# hs-64-spi.net
KiCad netlist of a schematic drawn in EAGLE
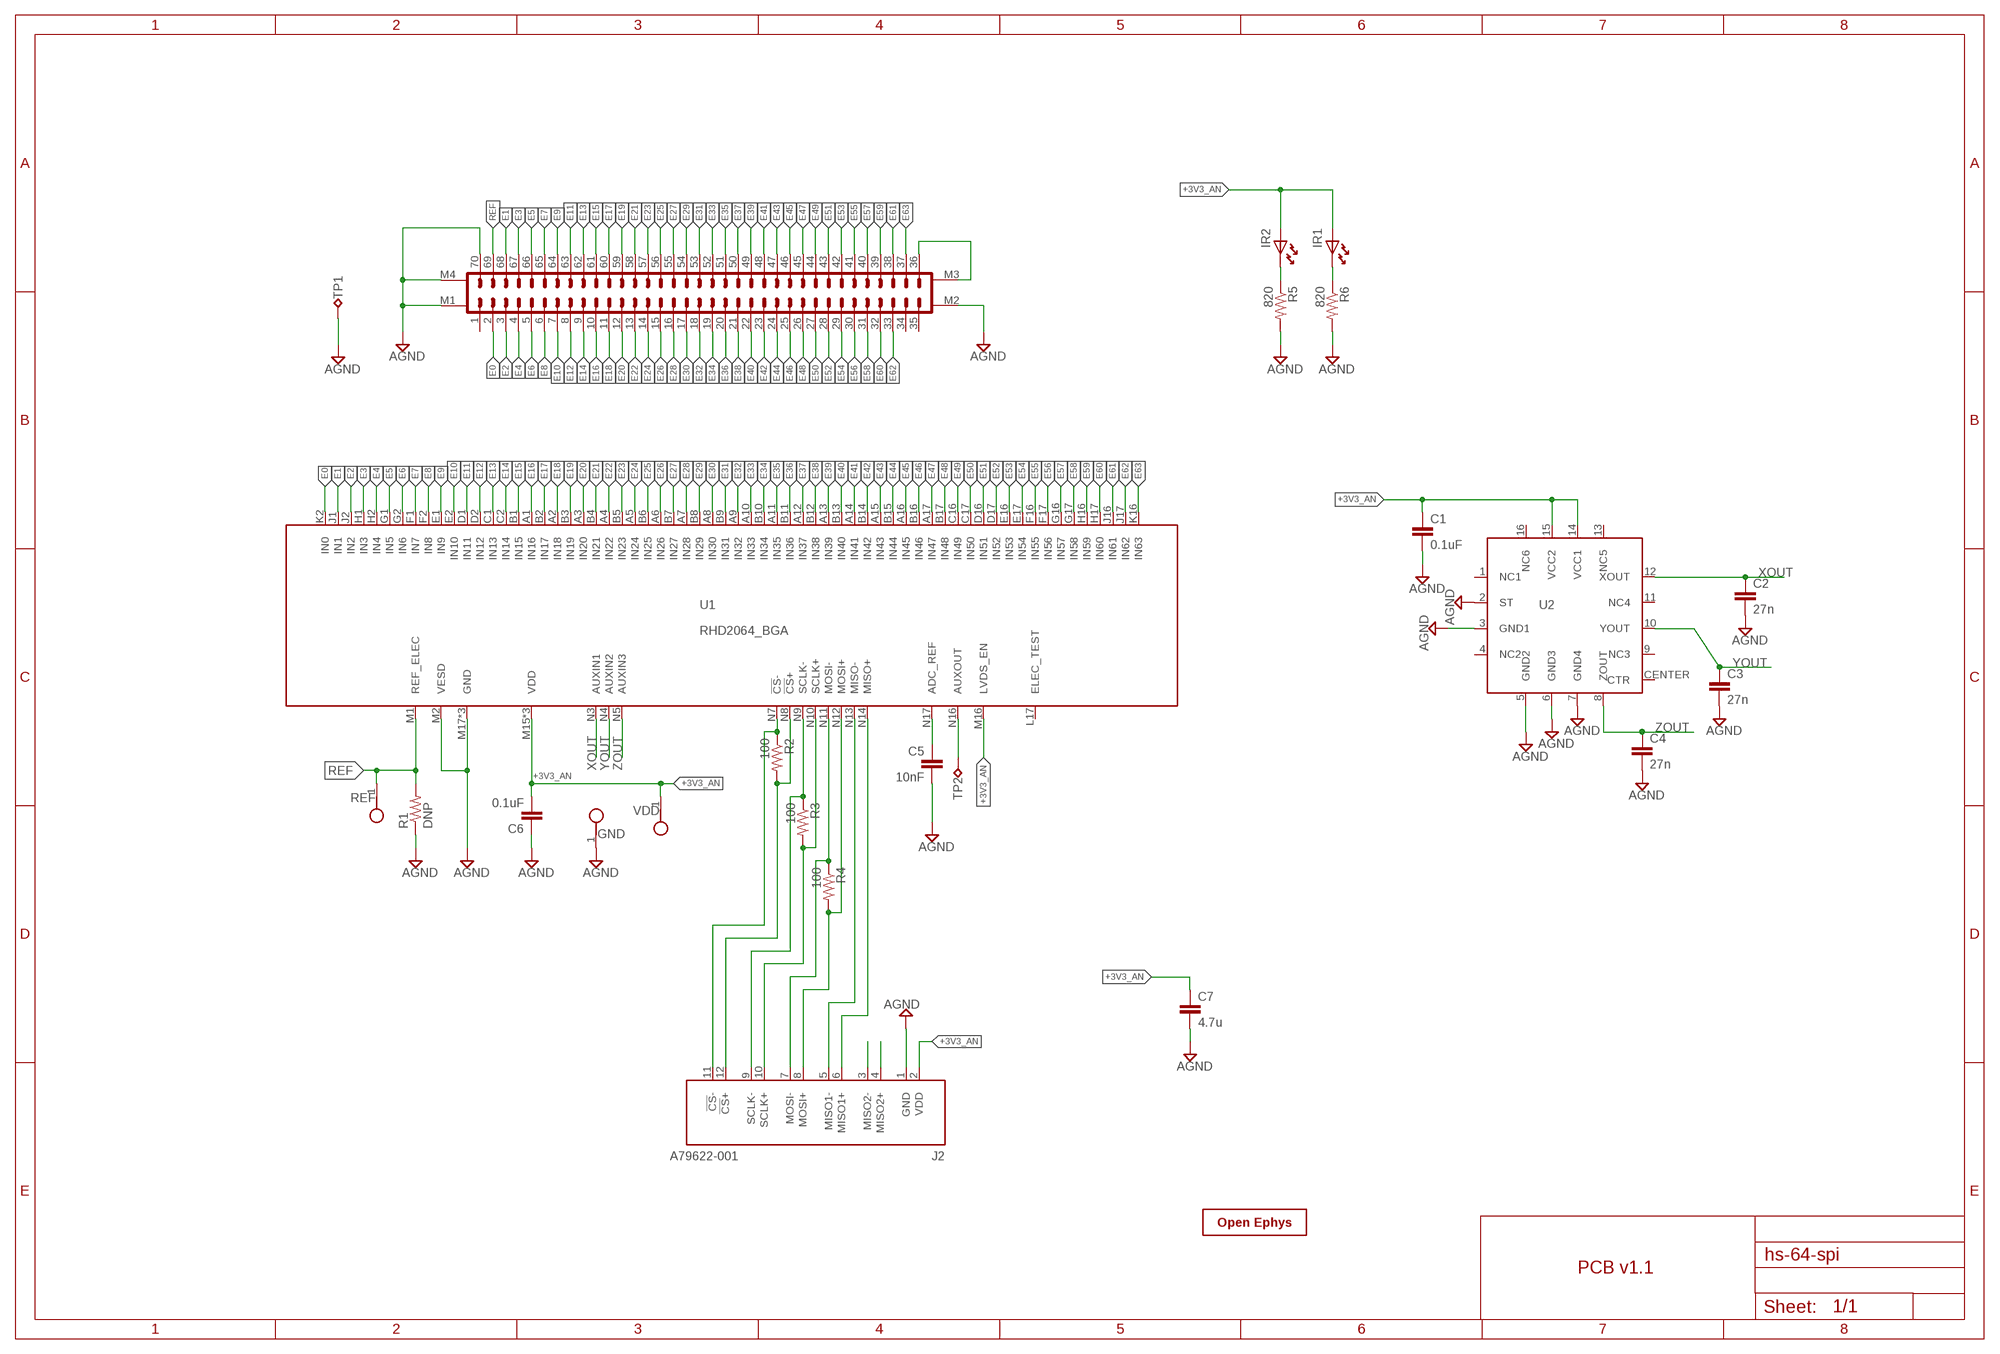
[diagram p0: schematic, sheet 1]

(export (version "E")
  (design (tool "Eeschema 10.0.6"))
  (components
    (comp (ref "C1")
      (value "0.1uF")
      (footprint "eagle-import:0402")
      (libsource (lib "eagle-import") (part "C_0402"))
    )
    (comp (ref "C2")
      (value "27n")
      (footprint "eagle-import:0402")
      (libsource (lib "eagle-import") (part "C_0402"))
    )
    (comp (ref "C3")
      (value "27n")
      (footprint "eagle-import:0402")
      (libsource (lib "eagle-import") (part "C_0402"))
    )
    (comp (ref "C4")
      (value "27n")
      (footprint "eagle-import:0402")
      (libsource (lib "eagle-import") (part "C_0402"))
    )
    (comp (ref "C5")
      (value "10nF")
      (footprint "eagle-import:0402T")
      (fields (field (name "PARTNO") "GRM033R71E103KE14D"))
      (libsource (lib "eagle-import") (part "C_0402T"))
    )
    (comp (ref "C6")
      (value "0.1uF")
      (footprint "eagle-import:0402T")
      (libsource (lib "eagle-import") (part "C_0402T"))
    )
    (comp (ref "C7")
      (value "4.7u")
      (footprint "eagle-import:0402")
      (libsource (lib "eagle-import") (part "C_0402"))
    )
    (comp (ref "GND")
      (value "TESTPOINT_SMALL")
      (footprint "eagle-import:TESTPOINT_SMALL")
      (libsource (lib "eagle-import") (part "TESTPOINT_SMALL"))
    )
    (comp (ref "IR1")
      (value "LEDHAND")
      (footprint "eagle-import:LED_HAND")
      (libsource (lib "eagle-import") (part "LEDHAND"))
    )
    (comp (ref "IR2")
      (value "LEDHAND")
      (footprint "eagle-import:LED_HAND")
      (libsource (lib "eagle-import") (part "LEDHAND"))
    )
    (comp (ref "J1")
      (value "DF40C-70DP-0.4V(51)")
      (footprint "eagle-import:DF40-70HEAD-LESS-SILK")
      (libsource (lib "eagle-import") (part "PINHD-2X35+4DF40-70HEAD-LESS-SILK"))
    )
    (comp (ref "J2")
      (value "A79622-001")
      (footprint "eagle-import:A79622-001")
      (libsource (lib "eagle-import") (part "A79622-001"))
    )
    (comp (ref "R1")
      (value "DNP")
      (footprint "eagle-import:0603")
      (fields (field (name "MPN") "ERJ-3EKFxxxxV"))
      (libsource (lib "eagle-import") (part "R_0603"))
    )
    (comp (ref "R2")
      (value "100")
      (footprint "eagle-import:0402")
      (libsource (lib "eagle-import") (part "R_0402"))
    )
    (comp (ref "R3")
      (value "100")
      (footprint "eagle-import:0402")
      (libsource (lib "eagle-import") (part "R_0402"))
    )
    (comp (ref "R4")
      (value "100")
      (footprint "eagle-import:0402")
      (libsource (lib "eagle-import") (part "R_0402"))
    )
    (comp (ref "R5")
      (value "820")
      (footprint "eagle-import:0402")
      (libsource (lib "eagle-import") (part "R_0402"))
    )
    (comp (ref "R6")
      (value "820")
      (footprint "eagle-import:0402")
      (libsource (lib "eagle-import") (part "R_0402"))
    )
    (comp (ref "REF")
      (value "TESTPOINT_SMALL")
      (footprint "eagle-import:TESTPOINT_SMALL")
      (libsource (lib "eagle-import") (part "TESTPOINT_SMALL"))
    )
    (comp (ref "TP1")
      (value "VCC")
      (footprint "eagle-import:TP07R")
      (libsource (lib "eagle-import") (part "TPTP07R"))
    )
    (comp (ref "TP2")
      (value "VCC")
      (footprint "eagle-import:TP07R")
      (libsource (lib "eagle-import") (part "TPTP07R"))
    )
    (comp (ref "U1")
      (value "RHD2064_BGA")
      (footprint "eagle-import:BGA104_0.5MM")
      (libsource (lib "eagle-import") (part "RHD2164_BGA_BGA"))
    )
    (comp (ref "U2")
      (value "ADXL335_IDAX")
      (footprint "eagle-import:ADXL335_IDAX")
      (libsource (lib "eagle-import") (part "ADXL335_IDAX"))
    )
    (comp (ref "VDD")
      (value "TESTPOINT_SMALL")
      (footprint "eagle-import:TESTPOINT_SMALL")
      (libsource (lib "eagle-import") (part "TESTPOINT_SMALL"))
    )
    (comp (ref "X")
      (value "OE-LOGO_3.5X2.5")
      (footprint "eagle-import:OE-LOGO-3.5X2.5")
      (libsource (lib "eagle-import") (part "OE-LOGO_3.5X2.5"))
    )
  )
  (nets
    (net (code "1") (name "+3V3_AN") (class "Default")
      (node (ref "C1") (pin "1") (pinfunction "1_1") (pintype "passive"))
      (node (ref "C6") (pin "2") (pinfunction "2_2") (pintype "passive"))
      (node (ref "C7") (pin "1") (pinfunction "1_1") (pintype "passive"))
      (node (ref "IR1") (pin "A") (pinfunction "A_A") (pintype "bidirectional"))
      (node (ref "IR2") (pin "A") (pinfunction "A_A") (pintype "bidirectional"))
      (node (ref "J2") (pin "2") (pinfunction "VDD_2") (pintype "bidirectional"))
      (node (ref "U1") (pin "M15") (pinfunction "VDD_M15") (pintype "power_in"))
      (node (ref "U1") (pin "M16") (pinfunction "LVDS_EN_M16") (pintype "input"))
      (node (ref "U1") (pin "N15") (pinfunction "VDD_N15") (pintype "power_in"))
      (node (ref "U1") (pin "N2") (pinfunction "VDD_N2") (pintype "power_in"))
      (node (ref "U2") (pin "14") (pinfunction "VCC1_14") (pintype "power_in"))
      (node (ref "U2") (pin "15") (pinfunction "VCC2_15") (pintype "power_in"))
      (node (ref "VDD") (pin "1") (pinfunction "1_1") (pintype "passive"))
    )
    (net (code "2") (name "/XOUT") (class "Default")
      (node (ref "C2") (pin "1") (pinfunction "1_1") (pintype "passive"))
      (node (ref "U1") (pin "N3") (pinfunction "AUXIN1_N3") (pintype "input"))
      (node (ref "U2") (pin "12") (pinfunction "XOUT_12") (pintype "output"))
    )
    (net (code "3") (name "/YOUT") (class "Default")
      (node (ref "C3") (pin "1") (pinfunction "1_1") (pintype "passive"))
      (node (ref "U1") (pin "N4") (pinfunction "AUXIN2_N4") (pintype "input"))
      (node (ref "U2") (pin "10") (pinfunction "YOUT_10") (pintype "output"))
    )
    (net (code "4") (name "/ZOUT") (class "Default")
      (node (ref "C4") (pin "1") (pinfunction "1_1") (pintype "passive"))
      (node (ref "U1") (pin "N5") (pinfunction "AUXIN3_N5") (pintype "input"))
      (node (ref "U2") (pin "8") (pinfunction "ZOUT_8") (pintype "output"))
    )
    (net (code "5") (name "AGND") (class "Default")
      (node (ref "C1") (pin "2") (pinfunction "2_2") (pintype "passive"))
      (node (ref "C2") (pin "2") (pinfunction "2_2") (pintype "passive"))
      (node (ref "C3") (pin "2") (pinfunction "2_2") (pintype "passive"))
      (node (ref "C4") (pin "2") (pinfunction "2_2") (pintype "passive"))
      (node (ref "C5") (pin "2") (pinfunction "2_2") (pintype "passive"))
      (node (ref "C6") (pin "1") (pinfunction "1_1") (pintype "passive"))
      (node (ref "C7") (pin "2") (pinfunction "2_2") (pintype "passive"))
      (node (ref "GND") (pin "1") (pinfunction "1_1") (pintype "passive"))
      (node (ref "J1") (pin "70") (pinfunction "70_70") (pintype "bidirectional"))
      (node (ref "J1") (pin "M1") (pinfunction "M1_M1") (pintype "bidirectional"))
      (node (ref "J1") (pin "M2") (pinfunction "M2_M2") (pintype "bidirectional"))
      (node (ref "J1") (pin "M4") (pinfunction "M4_M4") (pintype "bidirectional"))
      (node (ref "J2") (pin "1") (pinfunction "GND_1") (pintype "power_in"))
      (node (ref "R1") (pin "1") (pinfunction "1_1") (pintype "passive"))
      (node (ref "R5") (pin "2") (pinfunction "2_2") (pintype "passive"))
      (node (ref "R6") (pin "2") (pinfunction "2_2") (pintype "passive"))
      (node (ref "TP1") (pin "TP") (pinfunction "TP_TP") (pintype "bidirectional"))
      (node (ref "U1") (pin "M17") (pinfunction "GND_M17") (pintype "power_in"))
      (node (ref "U1") (pin "M2") (pinfunction "VESD_M2") (pintype "power_in"))
      (node (ref "U1") (pin "N1") (pinfunction "GND_N1") (pintype "power_in"))
      (node (ref "U1") (pin "N6") (pinfunction "GND_N6") (pintype "power_in"))
      (node (ref "U2") (pin "2") (pinfunction "ST_2") (pintype "input"))
      (node (ref "U2") (pin "3") (pinfunction "GND1_3") (pintype "power_in"))
      (node (ref "U2") (pin "5") (pinfunction "GND2_5") (pintype "power_in"))
      (node (ref "U2") (pin "6") (pinfunction "GND3_6") (pintype "power_in"))
      (node (ref "U2") (pin "7") (pinfunction "GND4_7") (pintype "power_in"))
    )
    (net (code "6") (name "E0") (class "Default")
      (node (ref "J1") (pin "2") (pinfunction "2_2") (pintype "bidirectional"))
      (node (ref "U1") (pin "K2") (pinfunction "IN0_K2") (pintype "input"))
    )
    (net (code "7") (name "E1") (class "Default")
      (node (ref "J1") (pin "68") (pinfunction "68_68") (pintype "bidirectional"))
      (node (ref "U1") (pin "J1") (pinfunction "IN1_J1") (pintype "input"))
    )
    (net (code "8") (name "E2") (class "Default")
      (node (ref "J1") (pin "3") (pinfunction "3_3") (pintype "bidirectional"))
      (node (ref "U1") (pin "J2") (pinfunction "IN2_J2") (pintype "input"))
    )
    (net (code "9") (name "E3") (class "Default")
      (node (ref "J1") (pin "67") (pinfunction "67_67") (pintype "bidirectional"))
      (node (ref "U1") (pin "H1") (pinfunction "IN3_H1") (pintype "input"))
    )
    (net (code "10") (name "E4") (class "Default")
      (node (ref "J1") (pin "4") (pinfunction "4_4") (pintype "bidirectional"))
      (node (ref "U1") (pin "H2") (pinfunction "IN4_H2") (pintype "input"))
    )
    (net (code "11") (name "E5") (class "Default")
      (node (ref "J1") (pin "66") (pinfunction "66_66") (pintype "bidirectional"))
      (node (ref "U1") (pin "G1") (pinfunction "IN5_G1") (pintype "input"))
    )
    (net (code "12") (name "E6") (class "Default")
      (node (ref "J1") (pin "5") (pinfunction "5_5") (pintype "bidirectional"))
      (node (ref "U1") (pin "G2") (pinfunction "IN6_G2") (pintype "input"))
    )
    (net (code "13") (name "E7") (class "Default")
      (node (ref "J1") (pin "65") (pinfunction "65_65") (pintype "bidirectional"))
      (node (ref "U1") (pin "F1") (pinfunction "IN7_F1") (pintype "input"))
    )
    (net (code "14") (name "E8") (class "Default")
      (node (ref "J1") (pin "6") (pinfunction "6_6") (pintype "bidirectional"))
      (node (ref "U1") (pin "F2") (pinfunction "IN8_F2") (pintype "input"))
    )
    (net (code "15") (name "E9") (class "Default")
      (node (ref "J1") (pin "64") (pinfunction "64_64") (pintype "bidirectional"))
      (node (ref "U1") (pin "E1") (pinfunction "IN9_E1") (pintype "input"))
    )
    (net (code "16") (name "E10") (class "Default")
      (node (ref "J1") (pin "7") (pinfunction "7_7") (pintype "bidirectional"))
      (node (ref "U1") (pin "E2") (pinfunction "IN10_E2") (pintype "input"))
    )
    (net (code "17") (name "E11") (class "Default")
      (node (ref "J1") (pin "63") (pinfunction "63_63") (pintype "bidirectional"))
      (node (ref "U1") (pin "D1") (pinfunction "IN11_D1") (pintype "input"))
    )
    (net (code "18") (name "E12") (class "Default")
      (node (ref "J1") (pin "8") (pinfunction "8_8") (pintype "bidirectional"))
      (node (ref "U1") (pin "D2") (pinfunction "IN12_D2") (pintype "input"))
    )
    (net (code "19") (name "E13") (class "Default")
      (node (ref "J1") (pin "62") (pinfunction "62_62") (pintype "bidirectional"))
      (node (ref "U1") (pin "C1") (pinfunction "IN13_C1") (pintype "input"))
    )
    (net (code "20") (name "E14") (class "Default")
      (node (ref "J1") (pin "9") (pinfunction "9_9") (pintype "bidirectional"))
      (node (ref "U1") (pin "C2") (pinfunction "IN14_C2") (pintype "input"))
    )
    (net (code "21") (name "E15") (class "Default")
      (node (ref "J1") (pin "61") (pinfunction "61_61") (pintype "bidirectional"))
      (node (ref "U1") (pin "B1") (pinfunction "IN15_B1") (pintype "input"))
    )
    (net (code "22") (name "E16") (class "Default")
      (node (ref "J1") (pin "10") (pinfunction "10_10") (pintype "bidirectional"))
      (node (ref "U1") (pin "A1") (pinfunction "IN16_A1") (pintype "input"))
    )
    (net (code "23") (name "E17") (class "Default")
      (node (ref "J1") (pin "60") (pinfunction "60_60") (pintype "bidirectional"))
      (node (ref "U1") (pin "B2") (pinfunction "IN17_B2") (pintype "input"))
    )
    (net (code "24") (name "E18") (class "Default")
      (node (ref "J1") (pin "11") (pinfunction "11_11") (pintype "bidirectional"))
      (node (ref "U1") (pin "A2") (pinfunction "IN18_A2") (pintype "input"))
    )
    (net (code "25") (name "E19") (class "Default")
      (node (ref "J1") (pin "59") (pinfunction "59_59") (pintype "bidirectional"))
      (node (ref "U1") (pin "B3") (pinfunction "IN19_B3") (pintype "input"))
    )
    (net (code "26") (name "E20") (class "Default")
      (node (ref "J1") (pin "12") (pinfunction "12_12") (pintype "bidirectional"))
      (node (ref "U1") (pin "A3") (pinfunction "IN20_A3") (pintype "input"))
    )
    (net (code "27") (name "E21") (class "Default")
      (node (ref "J1") (pin "58") (pinfunction "58_58") (pintype "bidirectional"))
      (node (ref "U1") (pin "B4") (pinfunction "IN21_B4") (pintype "input"))
    )
    (net (code "28") (name "E22") (class "Default")
      (node (ref "J1") (pin "13") (pinfunction "13_13") (pintype "bidirectional"))
      (node (ref "U1") (pin "A4") (pinfunction "IN22_A4") (pintype "input"))
    )
    (net (code "29") (name "E23") (class "Default")
      (node (ref "J1") (pin "57") (pinfunction "57_57") (pintype "bidirectional"))
      (node (ref "U1") (pin "B5") (pinfunction "IN23_B5") (pintype "input"))
    )
    (net (code "30") (name "E24") (class "Default")
      (node (ref "J1") (pin "14") (pinfunction "14_14") (pintype "bidirectional"))
      (node (ref "U1") (pin "A5") (pinfunction "IN24_A5") (pintype "input"))
    )
    (net (code "31") (name "E25") (class "Default")
      (node (ref "J1") (pin "56") (pinfunction "56_56") (pintype "bidirectional"))
      (node (ref "U1") (pin "B6") (pinfunction "IN25_B6") (pintype "input"))
    )
    (net (code "32") (name "E26") (class "Default")
      (node (ref "J1") (pin "15") (pinfunction "15_15") (pintype "bidirectional"))
      (node (ref "U1") (pin "A6") (pinfunction "IN26_A6") (pintype "input"))
    )
    (net (code "33") (name "E27") (class "Default")
      (node (ref "J1") (pin "55") (pinfunction "55_55") (pintype "bidirectional"))
      (node (ref "U1") (pin "B7") (pinfunction "IN27_B7") (pintype "input"))
    )
    (net (code "34") (name "E28") (class "Default")
      (node (ref "J1") (pin "16") (pinfunction "16_16") (pintype "bidirectional"))
      (node (ref "U1") (pin "A7") (pinfunction "IN28_A7") (pintype "input"))
    )
    (net (code "35") (name "E29") (class "Default")
      (node (ref "J1") (pin "54") (pinfunction "54_54") (pintype "bidirectional"))
      (node (ref "U1") (pin "B8") (pinfunction "IN29_B8") (pintype "input"))
    )
    (net (code "36") (name "E30") (class "Default")
      (node (ref "J1") (pin "17") (pinfunction "17_17") (pintype "bidirectional"))
      (node (ref "U1") (pin "A8") (pinfunction "IN30_A8") (pintype "input"))
    )
    (net (code "37") (name "E31") (class "Default")
      (node (ref "J1") (pin "53") (pinfunction "53_53") (pintype "bidirectional"))
      (node (ref "U1") (pin "B9") (pinfunction "IN31_B9") (pintype "input"))
    )
    (net (code "38") (name "E32") (class "Default")
      (node (ref "J1") (pin "18") (pinfunction "18_18") (pintype "bidirectional"))
      (node (ref "U1") (pin "A9") (pinfunction "IN32_A9") (pintype "input"))
    )
    (net (code "39") (name "E33") (class "Default")
      (node (ref "J1") (pin "52") (pinfunction "52_52") (pintype "bidirectional"))
      (node (ref "U1") (pin "A10") (pinfunction "IN33_A10") (pintype "input"))
    )
    (net (code "40") (name "E34") (class "Default")
      (node (ref "J1") (pin "19") (pinfunction "19_19") (pintype "bidirectional"))
      (node (ref "U1") (pin "B10") (pinfunction "IN34_B10") (pintype "input"))
    )
    (net (code "41") (name "E35") (class "Default")
      (node (ref "J1") (pin "51") (pinfunction "51_51") (pintype "bidirectional"))
      (node (ref "U1") (pin "A11") (pinfunction "IN35_A11") (pintype "input"))
    )
    (net (code "42") (name "E36") (class "Default")
      (node (ref "J1") (pin "20") (pinfunction "20_20") (pintype "bidirectional"))
      (node (ref "U1") (pin "B11") (pinfunction "IN36_B11") (pintype "input"))
    )
    (net (code "43") (name "E37") (class "Default")
      (node (ref "J1") (pin "50") (pinfunction "50_50") (pintype "bidirectional"))
      (node (ref "U1") (pin "A12") (pinfunction "IN37_A12") (pintype "input"))
    )
    (net (code "44") (name "E38") (class "Default")
      (node (ref "J1") (pin "21") (pinfunction "21_21") (pintype "bidirectional"))
      (node (ref "U1") (pin "B12") (pinfunction "IN38_B12") (pintype "input"))
    )
    (net (code "45") (name "E39") (class "Default")
      (node (ref "J1") (pin "49") (pinfunction "49_49") (pintype "bidirectional"))
      (node (ref "U1") (pin "A13") (pinfunction "IN39_A13") (pintype "input"))
    )
    (net (code "46") (name "E40") (class "Default")
      (node (ref "J1") (pin "22") (pinfunction "22_22") (pintype "bidirectional"))
      (node (ref "U1") (pin "B13") (pinfunction "IN40_B13") (pintype "input"))
    )
    (net (code "47") (name "E41") (class "Default")
      (node (ref "J1") (pin "48") (pinfunction "48_48") (pintype "bidirectional"))
      (node (ref "U1") (pin "A14") (pinfunction "IN41_A14") (pintype "input"))
    )
    (net (code "48") (name "E42") (class "Default")
      (node (ref "J1") (pin "23") (pinfunction "23_23") (pintype "bidirectional"))
      (node (ref "U1") (pin "B14") (pinfunction "IN42_B14") (pintype "input"))
    )
    (net (code "49") (name "E43") (class "Default")
      (node (ref "J1") (pin "47") (pinfunction "47_47") (pintype "bidirectional"))
      (node (ref "U1") (pin "A15") (pinfunction "IN43_A15") (pintype "input"))
    )
    (net (code "50") (name "E44") (class "Default")
      (node (ref "J1") (pin "24") (pinfunction "24_24") (pintype "bidirectional"))
      (node (ref "U1") (pin "B15") (pinfunction "IN44_B15") (pintype "input"))
    )
    (net (code "51") (name "E45") (class "Default")
      (node (ref "J1") (pin "46") (pinfunction "46_46") (pintype "bidirectional"))
      (node (ref "U1") (pin "A16") (pinfunction "IN45_A16") (pintype "input"))
    )
    (net (code "52") (name "E46") (class "Default")
      (node (ref "J1") (pin "25") (pinfunction "25_25") (pintype "bidirectional"))
      (node (ref "U1") (pin "B16") (pinfunction "IN46_B16") (pintype "input"))
    )
    (net (code "53") (name "E47") (class "Default")
      (node (ref "J1") (pin "45") (pinfunction "45_45") (pintype "bidirectional"))
      (node (ref "U1") (pin "A17") (pinfunction "IN47_A17") (pintype "input"))
    )
    (net (code "54") (name "E48") (class "Default")
      (node (ref "J1") (pin "26") (pinfunction "26_26") (pintype "bidirectional"))
      (node (ref "U1") (pin "B17") (pinfunction "IN48_B17") (pintype "input"))
    )
    (net (code "55") (name "E49") (class "Default")
      (node (ref "J1") (pin "44") (pinfunction "44_44") (pintype "bidirectional"))
      (node (ref "U1") (pin "C16") (pinfunction "IN49_C16") (pintype "input"))
    )
    (net (code "56") (name "E50") (class "Default")
      (node (ref "J1") (pin "27") (pinfunction "27_27") (pintype "bidirectional"))
      (node (ref "U1") (pin "C17") (pinfunction "IN50_C17") (pintype "input"))
    )
    (net (code "57") (name "E51") (class "Default")
      (node (ref "J1") (pin "43") (pinfunction "43_43") (pintype "bidirectional"))
      (node (ref "U1") (pin "D16") (pinfunction "IN51_D16") (pintype "input"))
    )
    (net (code "58") (name "E52") (class "Default")
      (node (ref "J1") (pin "28") (pinfunction "28_28") (pintype "bidirectional"))
      (node (ref "U1") (pin "D17") (pinfunction "IN52_D17") (pintype "input"))
    )
    (net (code "59") (name "E53") (class "Default")
      (node (ref "J1") (pin "42") (pinfunction "42_42") (pintype "bidirectional"))
      (node (ref "U1") (pin "E16") (pinfunction "IN53_E16") (pintype "input"))
    )
    (net (code "60") (name "E54") (class "Default")
      (node (ref "J1") (pin "29") (pinfunction "29_29") (pintype "bidirectional"))
      (node (ref "U1") (pin "E17") (pinfunction "IN54_E17") (pintype "input"))
    )
    (net (code "61") (name "E55") (class "Default")
      (node (ref "J1") (pin "41") (pinfunction "41_41") (pintype "bidirectional"))
      (node (ref "U1") (pin "F16") (pinfunction "IN55_F16") (pintype "input"))
    )
    (net (code "62") (name "E56") (class "Default")
      (node (ref "J1") (pin "30") (pinfunction "30_30") (pintype "bidirectional"))
      (node (ref "U1") (pin "F17") (pinfunction "IN56_F17") (pintype "input"))
    )
    (net (code "63") (name "E57") (class "Default")
      (node (ref "J1") (pin "40") (pinfunction "40_40") (pintype "bidirectional"))
      (node (ref "U1") (pin "G16") (pinfunction "IN57_G16") (pintype "input"))
    )
    (net (code "64") (name "E58") (class "Default")
      (node (ref "J1") (pin "31") (pinfunction "31_31") (pintype "bidirectional"))
      (node (ref "U1") (pin "G17") (pinfunction "IN58_G17") (pintype "input"))
    )
    (net (code "65") (name "E59") (class "Default")
      (node (ref "J1") (pin "39") (pinfunction "39_39") (pintype "bidirectional"))
      (node (ref "U1") (pin "H16") (pinfunction "IN59_H16") (pintype "input"))
    )
    (net (code "66") (name "E60") (class "Default")
      (node (ref "J1") (pin "32") (pinfunction "32_32") (pintype "bidirectional"))
      (node (ref "U1") (pin "H17") (pinfunction "IN60_H17") (pintype "input"))
    )
    (net (code "67") (name "E61") (class "Default")
      (node (ref "J1") (pin "38") (pinfunction "38_38") (pintype "bidirectional"))
      (node (ref "U1") (pin "J16") (pinfunction "IN61_J16") (pintype "input"))
    )
    (net (code "68") (name "E62") (class "Default")
      (node (ref "J1") (pin "33") (pinfunction "33_33") (pintype "bidirectional"))
      (node (ref "U1") (pin "J17") (pinfunction "IN62_J17") (pintype "input"))
    )
    (net (code "69") (name "E63") (class "Default")
      (node (ref "J1") (pin "37") (pinfunction "37_37") (pintype "bidirectional"))
      (node (ref "U1") (pin "K16") (pinfunction "IN63_K16") (pintype "input"))
    )
    (net (code "70") (name "Net-(IR1-PadK)") (class "Default")
      (node (ref "IR1") (pin "K") (pinfunction "K_K") (pintype "bidirectional"))
      (node (ref "R6") (pin "1") (pinfunction "1_1") (pintype "passive"))
    )
    (net (code "71") (name "Net-(IR2-PadK)") (class "Default")
      (node (ref "IR2") (pin "K") (pinfunction "K_K") (pintype "bidirectional"))
      (node (ref "R5") (pin "1") (pinfunction "1_1") (pintype "passive"))
    )
    (net (code "72") (name "Net-(J1-Pad36)") (class "Default")
      (node (ref "J1") (pin "36") (pinfunction "36_36") (pintype "bidirectional"))
      (node (ref "J1") (pin "M3") (pinfunction "M3_M3") (pintype "bidirectional"))
    )
    (net (code "73") (name "Net-(J2-MISO1+)") (class "Default")
      (node (ref "J2") (pin "6") (pinfunction "MISO1+_6") (pintype "bidirectional"))
      (node (ref "U1") (pin "N14") (pinfunction "MISO+_N14") (pintype "output"))
    )
    (net (code "74") (name "Net-(J2-MISO1-)") (class "Default")
      (node (ref "J2") (pin "5") (pinfunction "MISO1-_5") (pintype "bidirectional"))
      (node (ref "U1") (pin "N13") (pinfunction "MISO-_N13") (pintype "output"))
    )
    (net (code "75") (name "Net-(J2-MOSI+)") (class "Default")
      (node (ref "J2") (pin "8") (pinfunction "MOSI+_8") (pintype "bidirectional"))
      (node (ref "R4") (pin "2") (pinfunction "2_2") (pintype "passive"))
      (node (ref "U1") (pin "N12") (pinfunction "MOSI+_N12") (pintype "input"))
    )
    (net (code "76") (name "Net-(J2-MOSI-)") (class "Default")
      (node (ref "J2") (pin "7") (pinfunction "MOSI-_7") (pintype "bidirectional"))
      (node (ref "R4") (pin "1") (pinfunction "1_1") (pintype "passive"))
      (node (ref "U1") (pin "N11") (pinfunction "MOSI-_N11") (pintype "input"))
    )
    (net (code "77") (name "Net-(J2-SCLK+)") (class "Default")
      (node (ref "J2") (pin "10") (pinfunction "SCLK+_10") (pintype "bidirectional"))
      (node (ref "R3") (pin "2") (pinfunction "2_2") (pintype "passive"))
      (node (ref "U1") (pin "N10") (pinfunction "SCLK+_N10") (pintype "input"))
    )
    (net (code "78") (name "Net-(J2-SCLK-)") (class "Default")
      (node (ref "J2") (pin "9") (pinfunction "SCLK-_9") (pintype "bidirectional"))
      (node (ref "R3") (pin "1") (pinfunction "1_1") (pintype "passive"))
      (node (ref "U1") (pin "N9") (pinfunction "SCLK-_N9") (pintype "input"))
    )
    (net (code "79") (name "Net-(J2-~{CS}+)") (class "Default")
      (node (ref "J2") (pin "12") (pinfunction "~{CS}+_12") (pintype "bidirectional"))
      (node (ref "R2") (pin "2") (pinfunction "2_2") (pintype "passive"))
      (node (ref "U1") (pin "N8") (pinfunction "~{CS}+_N8") (pintype "input"))
    )
    (net (code "80") (name "Net-(J2-~{CS}-)") (class "Default")
      (node (ref "J2") (pin "11") (pinfunction "~{CS}-_11") (pintype "bidirectional"))
      (node (ref "R2") (pin "1") (pinfunction "1_1") (pintype "passive"))
      (node (ref "U1") (pin "N7") (pinfunction "~{CS}-_N7") (pintype "input"))
    )
    (net (code "81") (name "Net-(U1-ADC_REF)") (class "Default")
      (node (ref "C5") (pin "1") (pinfunction "1_1") (pintype "passive"))
      (node (ref "U1") (pin "N17") (pinfunction "ADC_REF_N17") (pintype "passive"))
    )
    (net (code "82") (name "Net-(U1-AUXOUT)") (class "Default")
      (node (ref "TP2") (pin "TP") (pinfunction "TP_TP") (pintype "bidirectional"))
      (node (ref "U1") (pin "N16") (pinfunction "AUXOUT_N16") (pintype "tri_state"))
    )
    (net (code "83") (name "REF") (class "Default")
      (node (ref "J1") (pin "69") (pinfunction "69_69") (pintype "bidirectional"))
      (node (ref "R1") (pin "2") (pinfunction "2_2") (pintype "passive"))
      (node (ref "REF") (pin "1") (pinfunction "1_1") (pintype "passive"))
      (node (ref "U1") (pin "M1") (pinfunction "REF_ELEC_M1") (pintype "input"))
    )
    (net (code "84") (name "unconnected-(J1-Pad1)") (class "Default")
      (node (ref "J1") (pin "1") (pinfunction "1_1") (pintype "bidirectional"))
    )
    (net (code "85") (name "unconnected-(J1-Pad34)") (class "Default")
      (node (ref "J1") (pin "34") (pinfunction "34_34") (pintype "bidirectional"))
    )
    (net (code "86") (name "unconnected-(J1-Pad35)") (class "Default")
      (node (ref "J1") (pin "35") (pinfunction "35_35") (pintype "bidirectional"))
    )
    (net (code "87") (name "unconnected-(J2-MISO2+-Pad4)") (class "Default")
      (node (ref "J2") (pin "4") (pinfunction "MISO2+_4") (pintype "bidirectional"))
    )
    (net (code "88") (name "unconnected-(J2-MISO2--Pad3)") (class "Default")
      (node (ref "J2") (pin "3") (pinfunction "MISO2-_3") (pintype "bidirectional"))
    )
    (net (code "89") (name "unconnected-(U1-ELEC_TEST-PadL17)") (class "Default")
      (node (ref "U1") (pin "L17") (pinfunction "ELEC_TEST_L17") (pintype "input"))
    )
    (net (code "90") (name "unconnected-(U2-CTR-PadCENTER)") (class "Default")
      (node (ref "U2") (pin "CENTER") (pinfunction "CTR_CENTER") (pintype "passive"))
    )
    (net (code "91") (name "unconnected-(U2-NC1-Pad1)") (class "Default")
      (node (ref "U2") (pin "1") (pinfunction "NC1_1") (pintype "no_connect"))
    )
    (net (code "92") (name "unconnected-(U2-NC2-Pad4)") (class "Default")
      (node (ref "U2") (pin "4") (pinfunction "NC2_4") (pintype "no_connect"))
    )
    (net (code "93") (name "unconnected-(U2-NC3-Pad9)") (class "Default")
      (node (ref "U2") (pin "9") (pinfunction "NC3_9") (pintype "no_connect"))
    )
    (net (code "94") (name "unconnected-(U2-NC4-Pad11)") (class "Default")
      (node (ref "U2") (pin "11") (pinfunction "NC4_11") (pintype "no_connect"))
    )
    (net (code "95") (name "unconnected-(U2-NC5-Pad13)") (class "Default")
      (node (ref "U2") (pin "13") (pinfunction "NC5_13") (pintype "no_connect"))
    )
    (net (code "96") (name "unconnected-(U2-NC6-Pad16)") (class "Default")
      (node (ref "U2") (pin "16") (pinfunction "NC6_16") (pintype "no_connect"))
    )
  )
)
